# as3320-BandPass.net
KiCad netlist of a schematic drawn in EAGLE
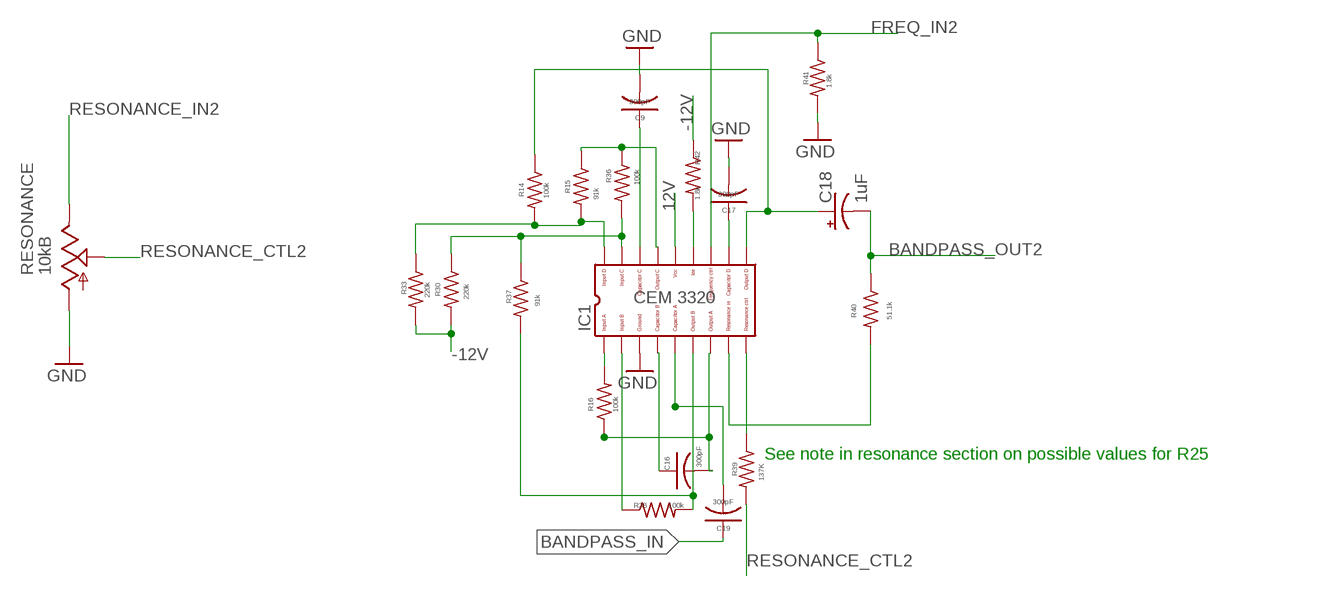
[diagram p0: schematic, sheet 1]
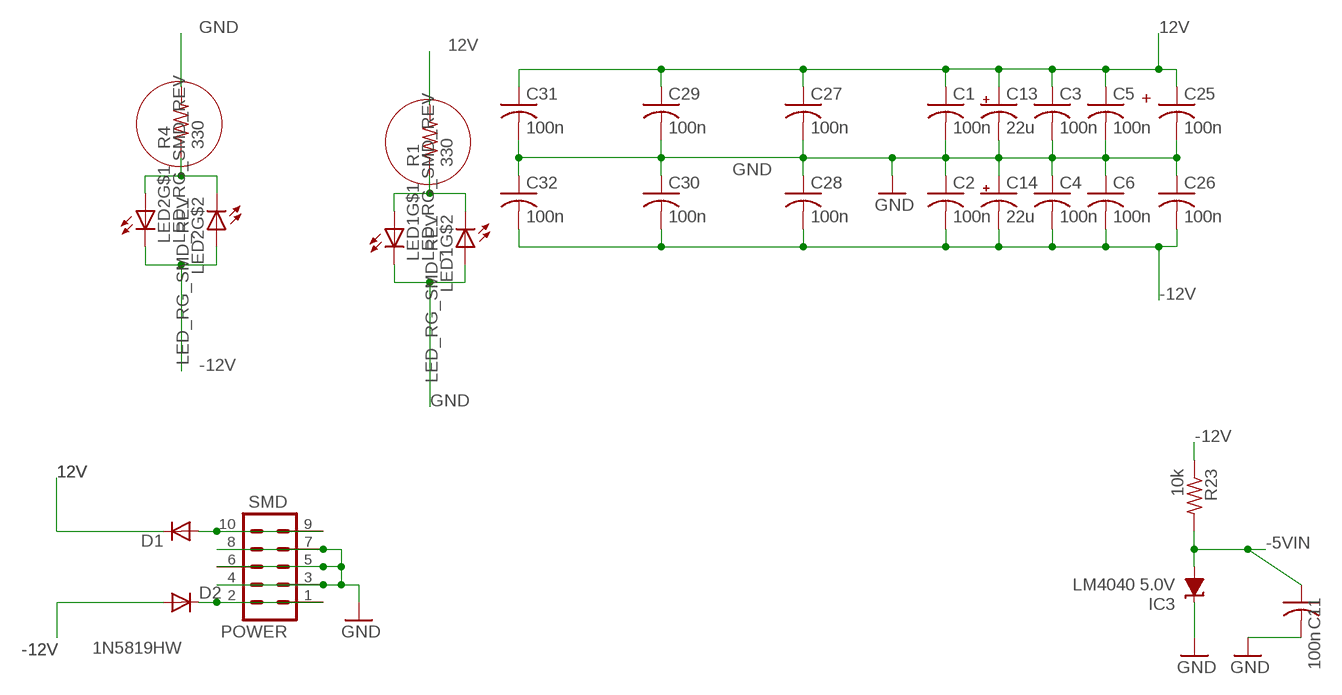
[diagram p1: schematic, sheet 2]
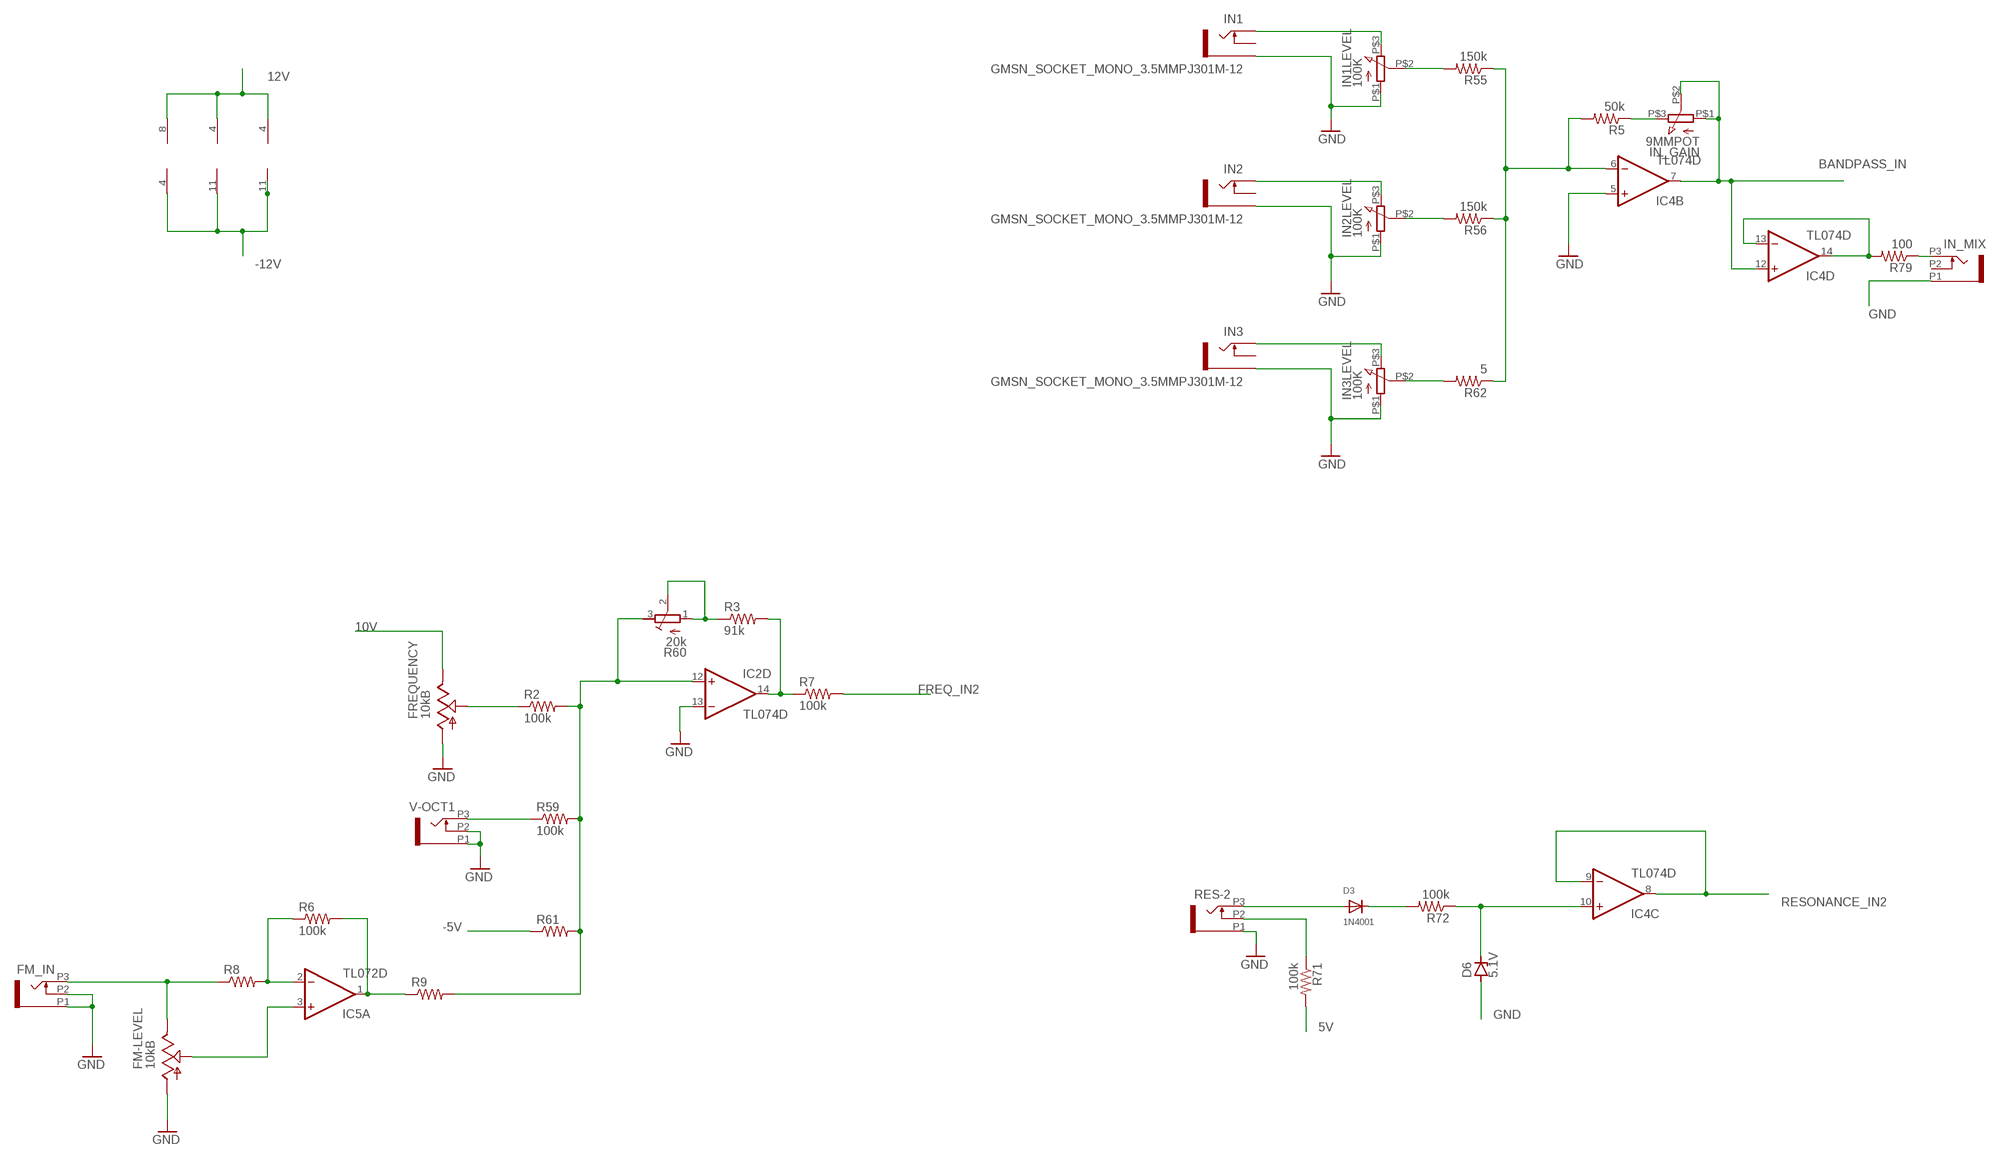
[diagram p2: schematic, sheet 3]
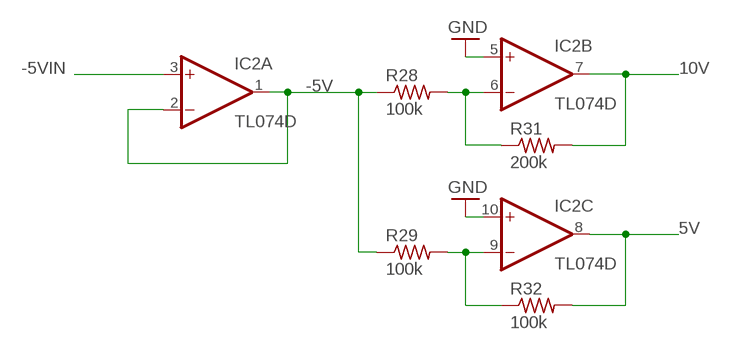
[diagram p3: schematic, sheet 4]
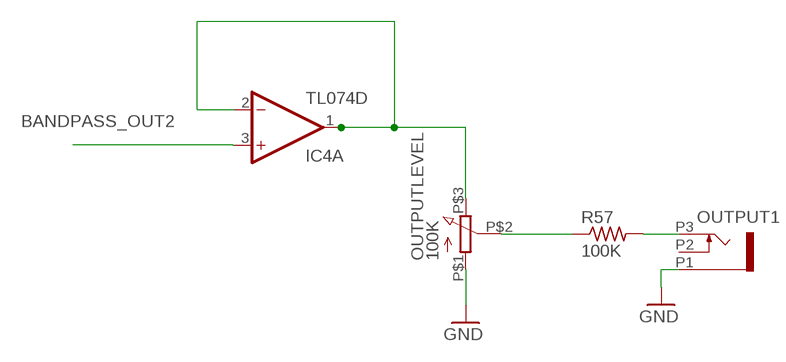
[diagram p4: schematic, sheet 5]

(export (version "E")
  (design (tool "Eeschema 10.0.6"))
  (components
    (comp (ref "C1")
      (value "100n")
      (footprint "eagle-import:C0805K")
      (libsource (lib "eagle-import") (part "C-USC0805K"))
    )
    (comp (ref "C2")
      (value "100n")
      (footprint "eagle-import:C0805K")
      (libsource (lib "eagle-import") (part "C-USC0805K"))
    )
    (comp (ref "C3")
      (value "100n")
      (footprint "eagle-import:C0805K")
      (libsource (lib "eagle-import") (part "C-USC0805K"))
    )
    (comp (ref "C4")
      (value "100n")
      (footprint "eagle-import:C0805K")
      (libsource (lib "eagle-import") (part "C-USC0805K"))
    )
    (comp (ref "C5")
      (value "100n")
      (footprint "eagle-import:C0805K")
      (libsource (lib "eagle-import") (part "C-USC0805K"))
    )
    (comp (ref "C6")
      (value "100n")
      (footprint "eagle-import:C0805K")
      (libsource (lib "eagle-import") (part "C-USC0805K"))
    )
    (comp (ref "C11")
      (value "100n")
      (footprint "eagle-import:GMSN_C0805K")
      (libsource (lib "eagle-import") (part "GMSN_C-USC0805K"))
    )
    (comp (ref "C13")
      (value "22u")
      (footprint "eagle-import:PANASONIC_B")
      (libsource (lib "eagle-import") (part "CPOL-USB"))
    )
    (comp (ref "C14")
      (value "22u")
      (footprint "eagle-import:PANASONIC_B")
      (libsource (lib "eagle-import") (part "CPOL-USB"))
    )
    (comp (ref "C25")
      (value "100n")
      (footprint "eagle-import:C0805K")
      (libsource (lib "eagle-import") (part "C-USC0805K"))
    )
    (comp (ref "C26")
      (value "100n")
      (footprint "eagle-import:C0805K")
      (libsource (lib "eagle-import") (part "C-USC0805K"))
    )
    (comp (ref "C27")
      (value "100n")
      (footprint "eagle-import:C0805K")
      (libsource (lib "eagle-import") (part "C-USC0805K"))
    )
    (comp (ref "C28")
      (value "100n")
      (footprint "eagle-import:C0805K")
      (libsource (lib "eagle-import") (part "C-USC0805K"))
    )
    (comp (ref "C29")
      (value "100n")
      (footprint "eagle-import:C0805K")
      (libsource (lib "eagle-import") (part "C-USC0805K"))
    )
    (comp (ref "C30")
      (value "100n")
      (footprint "eagle-import:C0805K")
      (libsource (lib "eagle-import") (part "C-USC0805K"))
    )
    (comp (ref "C31")
      (value "100n")
      (footprint "eagle-import:C0805K")
      (libsource (lib "eagle-import") (part "C-USC0805K"))
    )
    (comp (ref "C32")
      (value "100n")
      (footprint "eagle-import:C0805K")
      (libsource (lib "eagle-import") (part "C-USC0805K"))
    )
    (comp (ref "D1")
      (value "1N5819HW")
      (footprint "eagle-import:SOD123")
      (libsource (lib "eagle-import") (part "DIODE-SOD123"))
    )
    (comp (ref "D2")
      (value "1N5819HW")
      (footprint "eagle-import:SOD123")
      (libsource (lib "eagle-import") (part "DIODE-SOD123"))
    )
    (comp (ref "IC3")
      (value "LM4040 5.0V")
      (footprint "eagle-import:DBZ_R-PDSO-G3")
      (libsource (lib "eagle-import") (part "LM4041DBZC12"))
    )
    (comp (ref "LED1")
      (value "LED_RG_SMD_REV")
      (footprint "eagle-import:LSG_T77K")
      (fields (field (name "RS-PART") "915-4828"))
      (libsource (lib "eagle-import") (part "LED_RG_SMD_REV"))
    )
    (comp (ref "LED2")
      (value "LED_RG_SMD_REV")
      (footprint "eagle-import:LSG_T77K")
      (libsource (lib "eagle-import") (part "LED_RG_SMD_REV"))
    )
    (comp (ref "POWER")
      (value "SMD")
      (footprint "eagle-import:2X5-SHROUDED_SMD")
      (fields (field (name "RS-PART") "828-1783"))
      (libsource (lib "eagle-import") (part "CONN_05X2SHD_SMD"))
    )
    (comp (ref "R1")
      (value "330")
      (footprint "eagle-import:GMSN_M0805")
      (libsource (lib "eagle-import") (part "GMSN_R-US_M0805"))
    )
    (comp (ref "R4")
      (value "330")
      (footprint "eagle-import:GMSN_M0805")
      (fields (field (name "RS-PART") "915-4828"))
      (libsource (lib "eagle-import") (part "GMSN_R-US_M0805"))
    )
    (comp (ref "R23")
      (value "10k")
      (footprint "eagle-import:GMSN_M0805")
      (libsource (lib "eagle-import") (part "GMSN_R-US_M0805"))
    )
    (comp (ref "IC4")
      (value "TL074D")
      (footprint "eagle-import:SO14")
      (libsource (lib "eagle-import") (part "TL074D"))
    )
    (comp (ref "OUTPUT1")
      (value "PJ301_THONKICONN6")
      (footprint "eagle-import:WQP_PJ_301M6")
      (libsource (lib "eagle-import") (part "PJ301_THONKICONN6"))
    )
    (comp (ref "OUTPUTLEVEL")
      (value "100K")
      (footprint "eagle-import:POT")
      (libsource (lib "eagle-import") (part "9MMPOT"))
    )
    (comp (ref "R57")
      (value "100K")
      (footprint "eagle-import:GMSN_M0805")
      (libsource (lib "eagle-import") (part "GMSN_R-US_M0805"))
    )
    (comp (ref "D3")
      (value "1N4001")
      (footprint "eagle-import:SMADIODE")
      (libsource (lib "eagle-import") (part "DIODESMA"))
    )
    (comp (ref "D6")
      (value "5.1V")
      (footprint "eagle-import:SOT23")
      (fields (field (name "RS-PART") "816-7962"))
      (libsource (lib "eagle-import") (part "ZENER-DIODESOT23"))
    )
    (comp (ref "FM-LEVEL")
      (value "10kB")
      (footprint "eagle-import:ALPS_POT_VERTICAL")
      (libsource (lib "eagle-import") (part "POT_USVERTICAL"))
    )
    (comp (ref "FM_IN")
      (value "PJ301_THONKICONN6")
      (footprint "eagle-import:WQP_PJ_301M6")
      (libsource (lib "eagle-import") (part "PJ301_THONKICONN6"))
    )
    (comp (ref "FREQUENCY")
      (value "10kB")
      (footprint "eagle-import:ALPS_POT_VERTICAL")
      (libsource (lib "eagle-import") (part "POT_USVERTICAL"))
    )
    (comp (ref "IC2")
      (value "TL074D")
      (footprint "eagle-import:SO14")
      (libsource (lib "eagle-import") (part "linear_262_TL074D"))
    )
    (comp (ref "IC5")
      (value "TL072D")
      (footprint "eagle-import:SO08")
      (libsource (lib "eagle-import") (part "TL072D"))
    )
    (comp (ref "IN1")
      (value "GMSN_SOCKET_MONO_3.5MMPJ301M-12")
      (footprint "eagle-import:GMSN_PJ301M-12")
      (libsource (lib "eagle-import") (part "GMSN_SOCKET_MONO_3.5MMPJ301M-12"))
    )
    (comp (ref "IN1LEVEL")
      (value "100K")
      (footprint "eagle-import:POT")
      (libsource (lib "eagle-import") (part "9MMPOT"))
    )
    (comp (ref "IN2")
      (value "GMSN_SOCKET_MONO_3.5MMPJ301M-12")
      (footprint "eagle-import:GMSN_PJ301M-12")
      (libsource (lib "eagle-import") (part "GMSN_SOCKET_MONO_3.5MMPJ301M-12"))
    )
    (comp (ref "IN2LEVEL")
      (value "100K")
      (footprint "eagle-import:POT")
      (libsource (lib "eagle-import") (part "9MMPOT"))
    )
    (comp (ref "IN3")
      (value "GMSN_SOCKET_MONO_3.5MMPJ301M-12")
      (footprint "eagle-import:GMSN_PJ301M-12")
      (libsource (lib "eagle-import") (part "GMSN_SOCKET_MONO_3.5MMPJ301M-12"))
    )
    (comp (ref "IN3LEVEL")
      (value "100K")
      (footprint "eagle-import:POT")
      (libsource (lib "eagle-import") (part "9MMPOT"))
    )
    (comp (ref "IN_GAIN")
      (value "9MMPOT")
      (footprint "eagle-import:POT")
      (libsource (lib "eagle-import") (part "9MMPOT"))
    )
    (comp (ref "IN_MIX")
      (value "PJ301_THONKICONN6")
      (footprint "eagle-import:WQP_PJ_301M6")
      (libsource (lib "eagle-import") (part "PJ301_THONKICONN6"))
    )
    (comp (ref "R2")
      (value "100k")
      (footprint "eagle-import:GMSN_M0805")
      (libsource (lib "eagle-import") (part "GMSN_R-US_M0805"))
    )
    (comp (ref "R3")
      (value "91k")
      (footprint "eagle-import:GMSN_M0805")
      (libsource (lib "eagle-import") (part "GMSN_R-US_M0805"))
    )
    (comp (ref "R5")
      (value "50k")
      (footprint "eagle-import:GMSN_M0805")
      (libsource (lib "eagle-import") (part "GMSN_R-US_M0805"))
    )
    (comp (ref "R6")
      (value "100k")
      (footprint "eagle-import:GMSN_M0805")
      (libsource (lib "eagle-import") (part "GMSN_R-US_M0805"))
    )
    (comp (ref "R7")
      (value "100k")
      (footprint "eagle-import:GMSN_M0805")
      (libsource (lib "eagle-import") (part "GMSN_R-US_M0805"))
    )
    (comp (ref "R8")
      (value "62k")
      (footprint "eagle-import:GMSN_M0805")
      (libsource (lib "eagle-import") (part "GMSN_R-US_M0805"))
    )
    (comp (ref "R9")
      (value "62k")
      (footprint "eagle-import:GMSN_M0805")
      (libsource (lib "eagle-import") (part "GMSN_R-US_M0805"))
    )
    (comp (ref "R55")
      (value "150k")
      (footprint "eagle-import:R0805")
      (libsource (lib "eagle-import") (part "GMSN_R-US_R0805"))
    )
    (comp (ref "R56")
      (value "150k")
      (footprint "eagle-import:R0805")
      (libsource (lib "eagle-import") (part "GMSN_R-US_R0805"))
    )
    (comp (ref "R59")
      (value "100k")
      (footprint "eagle-import:GMSN_M0805")
      (libsource (lib "eagle-import") (part "GMSN_R-US_M0805"))
    )
    (comp (ref "R60")
      (value "20k")
      (footprint "eagle-import:RTRIM3296X")
      (libsource (lib "eagle-import") (part "R-TRIMM3296X"))
    )
    (comp (ref "R61")
      (value "62k")
      (footprint "eagle-import:GMSN_M0805")
      (libsource (lib "eagle-import") (part "GMSN_R-US_M0805"))
    )
    (comp (ref "R62")
      (value "5")
      (footprint "eagle-import:R0805")
      (libsource (lib "eagle-import") (part "GMSN_R-US_R0805"))
    )
    (comp (ref "R71")
      (value "100k")
      (footprint "eagle-import:R0805")
      (libsource (lib "eagle-import") (part "GMSN_R-US_R0805"))
    )
    (comp (ref "R72")
      (value "100k")
      (footprint "eagle-import:GMSN_M0805")
      (libsource (lib "eagle-import") (part "GMSN_R-US_M0805"))
    )
    (comp (ref "R79")
      (value "100")
      (footprint "eagle-import:GMSN_M0805")
      (libsource (lib "eagle-import") (part "GMSN_R-US_M0805"))
    )
    (comp (ref "RES-2")
      (value "PJ301_THONKICONN6")
      (footprint "eagle-import:WQP_PJ_301M6")
      (libsource (lib "eagle-import") (part "PJ301_THONKICONN6"))
    )
    (comp (ref "V-OCT1")
      (value "PJ301_THONKICONN6")
      (footprint "eagle-import:WQP_PJ_301M6")
      (libsource (lib "eagle-import") (part "PJ301_THONKICONN6"))
    )
    (comp (ref "C9")
      (value "300pF")
      (footprint "eagle-import:C0805K")
      (libsource (lib "eagle-import") (part "C-USC0805K"))
    )
    (comp (ref "C16")
      (value "300pF")
      (footprint "eagle-import:C0805K")
      (libsource (lib "eagle-import") (part "C-USC0805K"))
    )
    (comp (ref "C17")
      (value "300pF")
      (footprint "eagle-import:C0805K")
      (libsource (lib "eagle-import") (part "C-USC0805K"))
    )
    (comp (ref "C18")
      (value "1uF")
      (footprint "eagle-import:PANASONIC_B")
      (libsource (lib "eagle-import") (part "rcl_334_CPOL-USB"))
    )
    (comp (ref "C19")
      (value "300pF")
      (footprint "eagle-import:C0805K")
      (libsource (lib "eagle-import") (part "C-USC0805K"))
    )
    (comp (ref "IC1")
      (value "CEM3320")
      (footprint "eagle-import:DIL18")
      (libsource (lib "eagle-import") (part "CEM3320"))
    )
    (comp (ref "R14")
      (value "100k")
      (footprint "eagle-import:GMSN_M0805")
      (libsource (lib "eagle-import") (part "GMSN_R-US_M0805"))
    )
    (comp (ref "R15")
      (value "91k")
      (footprint "eagle-import:GMSN_M0805")
      (libsource (lib "eagle-import") (part "GMSN_R-US_M0805"))
    )
    (comp (ref "R16")
      (value "100k")
      (footprint "eagle-import:GMSN_M0805")
      (libsource (lib "eagle-import") (part "GMSN_R-US_M0805"))
    )
    (comp (ref "R30")
      (value "220k")
      (footprint "eagle-import:GMSN_M0805")
      (libsource (lib "eagle-import") (part "GMSN_R-US_M0805"))
    )
    (comp (ref "R33")
      (value "220k")
      (footprint "eagle-import:GMSN_M0805")
      (libsource (lib "eagle-import") (part "GMSN_R-US_M0805"))
    )
    (comp (ref "R36")
      (value "100k")
      (footprint "eagle-import:GMSN_M0805")
      (libsource (lib "eagle-import") (part "GMSN_R-US_M0805"))
    )
    (comp (ref "R37")
      (value "91k")
      (footprint "eagle-import:GMSN_M0805")
      (libsource (lib "eagle-import") (part "GMSN_R-US_M0805"))
    )
    (comp (ref "R38")
      (value "100k")
      (footprint "eagle-import:GMSN_M0805")
      (libsource (lib "eagle-import") (part "GMSN_R-US_M0805"))
    )
    (comp (ref "R39")
      (value "137K")
      (footprint "eagle-import:GMSN_M0805")
      (libsource (lib "eagle-import") (part "GMSN_R-US_M0805"))
    )
    (comp (ref "R40")
      (value "51.1k")
      (footprint "eagle-import:GMSN_M0805")
      (libsource (lib "eagle-import") (part "GMSN_R-US_M0805"))
    )
    (comp (ref "R41")
      (value "1.8k")
      (footprint "eagle-import:GMSN_M0805")
      (libsource (lib "eagle-import") (part "GMSN_R-US_M0805"))
    )
    (comp (ref "R42")
      (value "1.8k")
      (footprint "eagle-import:GMSN_M0805")
      (libsource (lib "eagle-import") (part "GMSN_R-US_M0805"))
    )
    (comp (ref "RESONANCE")
      (value "10kB")
      (footprint "eagle-import:ALPS_POT_VERTICAL")
      (libsource (lib "eagle-import") (part "POT_USVERTICAL"))
    )
    (comp (ref "R28")
      (value "100k")
      (footprint "eagle-import:GMSN_M0805")
      (libsource (lib "eagle-import") (part "GMSN_R-US_M0805"))
    )
    (comp (ref "R29")
      (value "100k")
      (footprint "eagle-import:GMSN_M0805")
      (libsource (lib "eagle-import") (part "GMSN_R-US_M0805"))
    )
    (comp (ref "R31")
      (value "200k")
      (footprint "eagle-import:GMSN_M0805")
      (libsource (lib "eagle-import") (part "GMSN_R-US_M0805"))
    )
    (comp (ref "R32")
      (value "100k")
      (footprint "eagle-import:GMSN_M0805")
      (libsource (lib "eagle-import") (part "GMSN_R-US_M0805"))
    )
  )
  (nets
    (net (code "1") (name "-5V") (class "Default")
      (node (ref "IC2") (pin "1") (pinfunction "OUT_1") (pintype "output"))
      (node (ref "IC2") (pin "2") (pinfunction "-IN_2") (pintype "input"))
      (node (ref "R28") (pin "1") (pinfunction "1_1") (pintype "passive"))
      (node (ref "R29") (pin "1") (pinfunction "1_1") (pintype "passive"))
      (node (ref "R61") (pin "1") (pinfunction "1_1") (pintype "passive"))
    )
    (net (code "2") (name "-5VIN") (class "Default")
      (node (ref "C11") (pin "1") (pinfunction "1_1") (pintype "passive"))
      (node (ref "IC2") (pin "3") (pinfunction "+IN_3") (pintype "input"))
      (node (ref "IC3") (pin "2") (pinfunction "A_2") (pintype "passive"))
      (node (ref "R23") (pin "2") (pinfunction "2_2") (pintype "passive"))
    )
    (net (code "3") (name "-12V") (class "Default")
      (node (ref "C14") (pin "-") (pinfunction "-_-") (pintype "passive"))
      (node (ref "C2") (pin "2") (pinfunction "2_2") (pintype "passive"))
      (node (ref "C26") (pin "2") (pinfunction "2_2") (pintype "passive"))
      (node (ref "C28") (pin "2") (pinfunction "2_2") (pintype "passive"))
      (node (ref "C30") (pin "2") (pinfunction "2_2") (pintype "passive"))
      (node (ref "C32") (pin "2") (pinfunction "2_2") (pintype "passive"))
      (node (ref "C4") (pin "2") (pinfunction "2_2") (pintype "passive"))
      (node (ref "C6") (pin "2") (pinfunction "2_2") (pintype "passive"))
      (node (ref "D2") (pin "A") (pinfunction "A_A") (pintype "passive"))
      (node (ref "IC2") (pin "11") (pinfunction "V-_11") (pintype "power_in"))
      (node (ref "IC4") (pin "11") (pinfunction "V-_11") (pintype "power_in"))
      (node (ref "IC5") (pin "4") (pinfunction "V-_4") (pintype "power_in"))
      (node (ref "LED2") (pin "1") (pinfunction "C_1") (pintype "passive"))
      (node (ref "LED2") (pin "4") (pinfunction "A_4") (pintype "passive"))
      (node (ref "R23") (pin "1") (pinfunction "1_1") (pintype "passive"))
      (node (ref "R30") (pin "2") (pinfunction "2_2") (pintype "passive"))
      (node (ref "R33") (pin "2") (pinfunction "2_2") (pintype "passive"))
      (node (ref "R42") (pin "1") (pinfunction "1_1") (pintype "passive"))
    )
    (net (code "4") (name "5V") (class "Default")
      (node (ref "IC2") (pin "8") (pinfunction "OUT_8") (pintype "output"))
      (node (ref "R32") (pin "2") (pinfunction "2_2") (pintype "passive"))
      (node (ref "R71") (pin "2") (pinfunction "2_2") (pintype "passive"))
    )
    (net (code "5") (name "10V") (class "Default")
      (node (ref "FREQUENCY") (pin "P$1") (pinfunction "E_P$1") (pintype "passive"))
      (node (ref "IC2") (pin "7") (pinfunction "OUT_7") (pintype "output"))
      (node (ref "R31") (pin "2") (pinfunction "2_2") (pintype "passive"))
    )
    (net (code "6") (name "12V") (class "Default")
      (node (ref "C1") (pin "1") (pinfunction "1_1") (pintype "passive"))
      (node (ref "C13") (pin "+") (pinfunction "+_+") (pintype "passive"))
      (node (ref "C25") (pin "1") (pinfunction "1_1") (pintype "passive"))
      (node (ref "C27") (pin "1") (pinfunction "1_1") (pintype "passive"))
      (node (ref "C29") (pin "1") (pinfunction "1_1") (pintype "passive"))
      (node (ref "C3") (pin "1") (pinfunction "1_1") (pintype "passive"))
      (node (ref "C31") (pin "1") (pinfunction "1_1") (pintype "passive"))
      (node (ref "C5") (pin "1") (pinfunction "1_1") (pintype "passive"))
      (node (ref "D1") (pin "C") (pinfunction "C_C") (pintype "passive"))
      (node (ref "IC1") (pin "14") (pinfunction "14_14") (pintype "power_in"))
      (node (ref "IC2") (pin "4") (pinfunction "V+_4") (pintype "power_in"))
      (node (ref "IC4") (pin "4") (pinfunction "V+_4") (pintype "power_in"))
      (node (ref "IC5") (pin "8") (pinfunction "V+_8") (pintype "power_in"))
      (node (ref "R1") (pin "2") (pinfunction "2_2") (pintype "passive"))
    )
    (net (code "7") (name "BANDPASS_IN") (class "Default")
      (node (ref "C19") (pin "1") (pinfunction "1_1") (pintype "passive"))
      (node (ref "IC4") (pin "12") (pinfunction "+IN_12") (pintype "input"))
      (node (ref "IC4") (pin "7") (pinfunction "OUT_7") (pintype "output"))
      (node (ref "IN_GAIN") (pin "P$1") (pinfunction "1_P$1") (pintype "passive"))
      (node (ref "IN_GAIN") (pin "P$2") (pinfunction "2_P$2") (pintype "passive"))
    )
    (net (code "8") (name "BANDPASS_OUT2") (class "Default")
      (node (ref "C18") (pin "-") (pinfunction "-_-") (pintype "passive"))
      (node (ref "IC4") (pin "3") (pinfunction "+IN_3") (pintype "input"))
      (node (ref "R40") (pin "1") (pinfunction "1_1") (pintype "passive"))
    )
    (net (code "9") (name "FREQ_IN2") (class "Default")
      (node (ref "IC1") (pin "12") (pinfunction "12_12") (pintype "bidirectional"))
      (node (ref "R41") (pin "1") (pinfunction "1_1") (pintype "passive"))
      (node (ref "R7") (pin "2") (pinfunction "2_2") (pintype "passive"))
    )
    (net (code "10") (name "GND") (class "Default")
      (node (ref "C1") (pin "2") (pinfunction "2_2") (pintype "passive"))
      (node (ref "C11") (pin "2") (pinfunction "2_2") (pintype "passive"))
      (node (ref "C13") (pin "-") (pinfunction "-_-") (pintype "passive"))
      (node (ref "C14") (pin "+") (pinfunction "+_+") (pintype "passive"))
      (node (ref "C17") (pin "2") (pinfunction "2_2") (pintype "passive"))
      (node (ref "C2") (pin "1") (pinfunction "1_1") (pintype "passive"))
      (node (ref "C25") (pin "2") (pinfunction "2_2") (pintype "passive"))
      (node (ref "C26") (pin "1") (pinfunction "1_1") (pintype "passive"))
      (node (ref "C27") (pin "2") (pinfunction "2_2") (pintype "passive"))
      (node (ref "C28") (pin "1") (pinfunction "1_1") (pintype "passive"))
      (node (ref "C29") (pin "2") (pinfunction "2_2") (pintype "passive"))
      (node (ref "C3") (pin "2") (pinfunction "2_2") (pintype "passive"))
      (node (ref "C30") (pin "1") (pinfunction "1_1") (pintype "passive"))
      (node (ref "C31") (pin "2") (pinfunction "2_2") (pintype "passive"))
      (node (ref "C32") (pin "1") (pinfunction "1_1") (pintype "passive"))
      (node (ref "C4") (pin "1") (pinfunction "1_1") (pintype "passive"))
      (node (ref "C5") (pin "2") (pinfunction "2_2") (pintype "passive"))
      (node (ref "C6") (pin "1") (pinfunction "1_1") (pintype "passive"))
      (node (ref "C9") (pin "2") (pinfunction "2_2") (pintype "passive"))
      (node (ref "D6") (pin "1") (pinfunction "A_1") (pintype "passive"))
      (node (ref "FM-LEVEL") (pin "P$3") (pinfunction "A_P$3") (pintype "passive"))
      (node (ref "FM_IN") (pin "P1") (pinfunction "1_P1") (pintype "passive"))
      (node (ref "FM_IN") (pin "P2") (pinfunction "2_P2") (pintype "passive"))
      (node (ref "FREQUENCY") (pin "P$3") (pinfunction "A_P$3") (pintype "passive"))
      (node (ref "IC1") (pin "3") (pinfunction "3_3") (pintype "power_in"))
      (node (ref "IC2") (pin "10") (pinfunction "+IN_10") (pintype "input"))
      (node (ref "IC2") (pin "13") (pinfunction "-IN_13") (pintype "input"))
      (node (ref "IC2") (pin "5") (pinfunction "+IN_5") (pintype "input"))
      (node (ref "IC3") (pin "1") (pinfunction "C_1") (pintype "passive"))
      (node (ref "IC4") (pin "5") (pinfunction "+IN_5") (pintype "input"))
      (node (ref "IN1") (pin "GND") (pinfunction "SLEEVE_GND") (pintype "passive"))
      (node (ref "IN1LEVEL") (pin "P$1") (pinfunction "1_P$1") (pintype "passive"))
      (node (ref "IN2") (pin "GND") (pinfunction "SLEEVE_GND") (pintype "passive"))
      (node (ref "IN2LEVEL") (pin "P$1") (pinfunction "1_P$1") (pintype "passive"))
      (node (ref "IN3") (pin "GND") (pinfunction "SLEEVE_GND") (pintype "passive"))
      (node (ref "IN3LEVEL") (pin "P$1") (pinfunction "1_P$1") (pintype "passive"))
      (node (ref "IN_MIX") (pin "P1") (pinfunction "1_P1") (pintype "passive"))
      (node (ref "LED1") (pin "1") (pinfunction "C_1") (pintype "passive"))
      (node (ref "LED1") (pin "4") (pinfunction "A_4") (pintype "passive"))
      (node (ref "OUTPUT1") (pin "P1") (pinfunction "1_P1") (pintype "passive"))
      (node (ref "OUTPUTLEVEL") (pin "P$1") (pinfunction "1_P$1") (pintype "passive"))
      (node (ref "POWER") (pin "3") (pinfunction "3_3") (pintype "passive"))
      (node (ref "POWER") (pin "4") (pinfunction "4_4") (pintype "passive"))
      (node (ref "POWER") (pin "5") (pinfunction "5_5") (pintype "passive"))
      (node (ref "POWER") (pin "6") (pinfunction "6_6") (pintype "passive"))
      (node (ref "POWER") (pin "7") (pinfunction "7_7") (pintype "passive"))
      (node (ref "POWER") (pin "8") (pinfunction "8_8") (pintype "passive"))
      (node (ref "R4") (pin "2") (pinfunction "2_2") (pintype "passive"))
      (node (ref "R41") (pin "2") (pinfunction "2_2") (pintype "passive"))
      (node (ref "RES-2") (pin "P1") (pinfunction "1_P1") (pintype "passive"))
      (node (ref "RESONANCE") (pin "P$3") (pinfunction "A_P$3") (pintype "passive"))
      (node (ref "V-OCT1") (pin "P1") (pinfunction "1_P1") (pintype "passive"))
      (node (ref "V-OCT1") (pin "P2") (pinfunction "2_P2") (pintype "passive"))
    )
    (net (code "11") (name "Net-(C9-Pad1)") (class "Default")
      (node (ref "C9") (pin "1") (pinfunction "1_1") (pintype "passive"))
      (node (ref "IC1") (pin "16") (pinfunction "16_16") (pintype "bidirectional"))
    )
    (net (code "12") (name "Net-(C16-Pad1)") (class "Default")
      (node (ref "C16") (pin "1") (pinfunction "1_1") (pintype "passive"))
      (node (ref "IC1") (pin "4") (pinfunction "4_4") (pintype "bidirectional"))
    )
    (net (code "13") (name "Net-(C16-Pad2)") (class "Default")
      (node (ref "C16") (pin "2") (pinfunction "2_2") (pintype "passive"))
      (node (ref "IC1") (pin "7") (pinfunction "7_7") (pintype "output"))
      (node (ref "R16") (pin "1") (pinfunction "1_1") (pintype "passive"))
    )
    (net (code "14") (name "Net-(C17-Pad1)") (class "Default")
      (node (ref "C17") (pin "1") (pinfunction "1_1") (pintype "passive"))
      (node (ref "IC1") (pin "11") (pinfunction "11_11") (pintype "output"))
    )
    (net (code "15") (name "Net-(C18-Pad+)") (class "Default")
      (node (ref "C18") (pin "+") (pinfunction "+_+") (pintype "passive"))
      (node (ref "IC1") (pin "10") (pinfunction "10_10") (pintype "output"))
      (node (ref "R14") (pin "1") (pinfunction "1_1") (pintype "passive"))
    )
    (net (code "16") (name "Net-(C19-Pad2)") (class "Default")
      (node (ref "C19") (pin "2") (pinfunction "2_2") (pintype "passive"))
      (node (ref "IC1") (pin "5") (pinfunction "5_5") (pintype "bidirectional"))
    )
    (net (code "17") (name "Net-(D1-PadA)") (class "Default")
      (node (ref "D1") (pin "A") (pinfunction "A_A") (pintype "passive"))
      (node (ref "POWER") (pin "10") (pinfunction "10_10") (pintype "passive"))
      (node (ref "POWER") (pin "9") (pinfunction "9_9") (pintype "passive"))
    )
    (net (code "18") (name "Net-(D2-PadC)") (class "Default")
      (node (ref "D2") (pin "C") (pinfunction "C_C") (pintype "passive"))
      (node (ref "POWER") (pin "1") (pinfunction "1_1") (pintype "passive"))
      (node (ref "POWER") (pin "2") (pinfunction "2_2") (pintype "passive"))
    )
    (net (code "19") (name "Net-(D3-PadC)") (class "Default")
      (node (ref "D3") (pin "C") (pinfunction "C_C") (pintype "passive"))
      (node (ref "R72") (pin "2") (pinfunction "2_2") (pintype "passive"))
    )
    (net (code "20") (name "Net-(D6-C)") (class "Default")
      (node (ref "D6") (pin "3") (pinfunction "C_3") (pintype "passive"))
      (node (ref "IC4") (pin "10") (pinfunction "+IN_10") (pintype "input"))
      (node (ref "R72") (pin "1") (pinfunction "1_1") (pintype "passive"))
    )
    (net (code "21") (name "Net-(FM-LEVEL-E)") (class "Default")
      (node (ref "FM-LEVEL") (pin "P$1") (pinfunction "E_P$1") (pintype "passive"))
      (node (ref "FM_IN") (pin "P3") (pinfunction "3_P3") (pintype "passive"))
      (node (ref "R8") (pin "1") (pinfunction "1_1") (pintype "passive"))
    )
    (net (code "22") (name "Net-(FM-LEVEL-S)") (class "Default")
      (node (ref "FM-LEVEL") (pin "P$2") (pinfunction "S_P$2") (pintype "passive"))
      (node (ref "IC5") (pin "3") (pinfunction "+IN_3") (pintype "input"))
    )
    (net (code "23") (name "Net-(FREQUENCY-S)") (class "Default")
      (node (ref "FREQUENCY") (pin "P$2") (pinfunction "S_P$2") (pintype "passive"))
      (node (ref "R2") (pin "1") (pinfunction "1_1") (pintype "passive"))
    )
    (net (code "24") (name "Net-(IC1-Pad1)") (class "Default")
      (node (ref "IC1") (pin "1") (pinfunction "1_1") (pintype "input"))
      (node (ref "R16") (pin "2") (pinfunction "2_2") (pintype "passive"))
    )
    (net (code "25") (name "Net-(IC1-Pad2)") (class "Default")
      (node (ref "IC1") (pin "2") (pinfunction "2_2") (pintype "input"))
      (node (ref "R38") (pin "1") (pinfunction "1_1") (pintype "passive"))
    )
    (net (code "26") (name "Net-(IC1-Pad6)") (class "Default")
      (node (ref "IC1") (pin "6") (pinfunction "6_6") (pintype "output"))
      (node (ref "R37") (pin "2") (pinfunction "2_2") (pintype "passive"))
      (node (ref "R38") (pin "2") (pinfunction "2_2") (pintype "passive"))
    )
    (net (code "27") (name "Net-(IC1-Pad8)") (class "Default")
      (node (ref "IC1") (pin "8") (pinfunction "8_8") (pintype "input"))
      (node (ref "R40") (pin "2") (pinfunction "2_2") (pintype "passive"))
    )
    (net (code "28") (name "Net-(IC1-Pad9)") (class "Default")
      (node (ref "IC1") (pin "9") (pinfunction "9_9") (pintype "input"))
      (node (ref "R39") (pin "1") (pinfunction "1_1") (pintype "passive"))
    )
    (net (code "29") (name "Net-(IC1-Pad13)") (class "Default")
      (node (ref "IC1") (pin "13") (pinfunction "13_13") (pintype "power_in"))
      (node (ref "R42") (pin "2") (pinfunction "2_2") (pintype "passive"))
    )
    (net (code "30") (name "Net-(IC1-Pad15)") (class "Default")
      (node (ref "IC1") (pin "15") (pinfunction "15_15") (pintype "output"))
      (node (ref "R15") (pin "1") (pinfunction "1_1") (pintype "passive"))
      (node (ref "R36") (pin "1") (pinfunction "1_1") (pintype "passive"))
    )
    (net (code "31") (name "Net-(IC1-Pad17)") (class "Default")
      (node (ref "IC1") (pin "17") (pinfunction "17_17") (pintype "input"))
      (node (ref "R30") (pin "1") (pinfunction "1_1") (pintype "passive"))
      (node (ref "R36") (pin "2") (pinfunction "2_2") (pintype "passive"))
      (node (ref "R37") (pin "1") (pinfunction "1_1") (pintype "passive"))
    )
    (net (code "32") (name "Net-(IC1-Pad18)") (class "Default")
      (node (ref "IC1") (pin "18") (pinfunction "18_18") (pintype "input"))
      (node (ref "R14") (pin "2") (pinfunction "2_2") (pintype "passive"))
      (node (ref "R15") (pin "2") (pinfunction "2_2") (pintype "passive"))
      (node (ref "R33") (pin "1") (pinfunction "1_1") (pintype "passive"))
    )
    (net (code "33") (name "Net-(IC2B--IN)") (class "Default")
      (node (ref "IC2") (pin "6") (pinfunction "-IN_6") (pintype "input"))
      (node (ref "R28") (pin "2") (pinfunction "2_2") (pintype "passive"))
      (node (ref "R31") (pin "1") (pinfunction "1_1") (pintype "passive"))
    )
    (net (code "34") (name "Net-(IC2C--IN)") (class "Default")
      (node (ref "IC2") (pin "9") (pinfunction "-IN_9") (pintype "input"))
      (node (ref "R29") (pin "2") (pinfunction "2_2") (pintype "passive"))
      (node (ref "R32") (pin "1") (pinfunction "1_1") (pintype "passive"))
    )
    (net (code "35") (name "Net-(IC2D-+IN)") (class "Default")
      (node (ref "IC2") (pin "12") (pinfunction "+IN_12") (pintype "input"))
      (node (ref "R2") (pin "2") (pinfunction "2_2") (pintype "passive"))
      (node (ref "R59") (pin "2") (pinfunction "2_2") (pintype "passive"))
      (node (ref "R60") (pin "3") (pinfunction "A_3") (pintype "passive"))
      (node (ref "R61") (pin "2") (pinfunction "2_2") (pintype "passive"))
      (node (ref "R9") (pin "2") (pinfunction "2_2") (pintype "passive"))
    )
    (net (code "36") (name "Net-(IC2D-OUT)") (class "Default")
      (node (ref "IC2") (pin "14") (pinfunction "OUT_14") (pintype "output"))
      (node (ref "R3") (pin "2") (pinfunction "2_2") (pintype "passive"))
      (node (ref "R7") (pin "1") (pinfunction "1_1") (pintype "passive"))
    )
    (net (code "37") (name "Net-(IC4A--IN)") (class "Default")
      (node (ref "IC4") (pin "1") (pinfunction "OUT_1") (pintype "output"))
      (node (ref "IC4") (pin "2") (pinfunction "-IN_2") (pintype "input"))
      (node (ref "OUTPUTLEVEL") (pin "P$3") (pinfunction "3_P$3") (pintype "passive"))
    )
    (net (code "38") (name "Net-(IC4B--IN)") (class "Default")
      (node (ref "IC4") (pin "6") (pinfunction "-IN_6") (pintype "input"))
      (node (ref "R5") (pin "2") (pinfunction "2_2") (pintype "passive"))
      (node (ref "R55") (pin "1") (pinfunction "1_1") (pintype "passive"))
      (node (ref "R56") (pin "1") (pinfunction "1_1") (pintype "passive"))
      (node (ref "R62") (pin "1") (pinfunction "1_1") (pintype "passive"))
    )
    (net (code "39") (name "Net-(IC4D--IN)") (class "Default")
      (node (ref "IC4") (pin "13") (pinfunction "-IN_13") (pintype "input"))
      (node (ref "IC4") (pin "14") (pinfunction "OUT_14") (pintype "output"))
      (node (ref "R79") (pin "2") (pinfunction "2_2") (pintype "passive"))
    )
    (net (code "40") (name "Net-(IC5A--IN)") (class "Default")
      (node (ref "IC5") (pin "2") (pinfunction "-IN_2") (pintype "input"))
      (node (ref "R6") (pin "1") (pinfunction "1_1") (pintype "passive"))
      (node (ref "R8") (pin "2") (pinfunction "2_2") (pintype "passive"))
    )
    (net (code "41") (name "Net-(IC5A-OUT)") (class "Default")
      (node (ref "IC5") (pin "1") (pinfunction "OUT_1") (pintype "output"))
      (node (ref "R6") (pin "2") (pinfunction "2_2") (pintype "passive"))
      (node (ref "R9") (pin "1") (pinfunction "1_1") (pintype "passive"))
    )
    (net (code "42") (name "Net-(IN1LEVEL-2)") (class "Default")
      (node (ref "IN1LEVEL") (pin "P$2") (pinfunction "2_P$2") (pintype "passive"))
      (node (ref "R55") (pin "2") (pinfunction "2_2") (pintype "passive"))
    )
    (net (code "43") (name "Net-(IN1LEVEL-3)") (class "Default")
      (node (ref "IN1") (pin "TIP") (pinfunction "TIP_TIP") (pintype "passive"))
      (node (ref "IN1LEVEL") (pin "P$3") (pinfunction "3_P$3") (pintype "passive"))
    )
    (net (code "44") (name "Net-(IN2LEVEL-2)") (class "Default")
      (node (ref "IN2LEVEL") (pin "P$2") (pinfunction "2_P$2") (pintype "passive"))
      (node (ref "R56") (pin "2") (pinfunction "2_2") (pintype "passive"))
    )
    (net (code "45") (name "Net-(IN2LEVEL-3)") (class "Default")
      (node (ref "IN2") (pin "TIP") (pinfunction "TIP_TIP") (pintype "passive"))
      (node (ref "IN2LEVEL") (pin "P$3") (pinfunction "3_P$3") (pintype "passive"))
    )
    (net (code "46") (name "Net-(IN3LEVEL-2)") (class "Default")
      (node (ref "IN3LEVEL") (pin "P$2") (pinfunction "2_P$2") (pintype "passive"))
      (node (ref "R62") (pin "2") (pinfunction "2_2") (pintype "passive"))
    )
    (net (code "47") (name "Net-(IN3LEVEL-3)") (class "Default")
      (node (ref "IN3") (pin "TIP") (pinfunction "TIP_TIP") (pintype "passive"))
      (node (ref "IN3LEVEL") (pin "P$3") (pinfunction "3_P$3") (pintype "passive"))
    )
    (net (code "48") (name "Net-(IN_GAIN-3)") (class "Default")
      (node (ref "IN_GAIN") (pin "P$3") (pinfunction "3_P$3") (pintype "passive"))
      (node (ref "R5") (pin "1") (pinfunction "1_1") (pintype "passive"))
    )
    (net (code "49") (name "Net-(IN_MIX-3)") (class "Default")
      (node (ref "IN_MIX") (pin "P3") (pinfunction "3_P3") (pintype "passive"))
      (node (ref "R79") (pin "1") (pinfunction "1_1") (pintype "passive"))
    )
    (net (code "50") (name "Net-(LED1A-A)") (class "Default")
      (node (ref "LED1") (pin "2") (pinfunction "A_2") (pintype "passive"))
      (node (ref "LED1") (pin "3") (pinfunction "C_3") (pintype "passive"))
      (node (ref "R1") (pin "1") (pinfunction "1_1") (pintype "passive"))
    )
    (net (code "51") (name "Net-(LED2A-A)") (class "Default")
      (node (ref "LED2") (pin "2") (pinfunction "A_2") (pintype "passive"))
      (node (ref "LED2") (pin "3") (pinfunction "C_3") (pintype "passive"))
      (node (ref "R4") (pin "1") (pinfunction "1_1") (pintype "passive"))
    )
    (net (code "52") (name "Net-(OUTPUT1-3)") (class "Default")
      (node (ref "OUTPUT1") (pin "P3") (pinfunction "3_P3") (pintype "passive"))
      (node (ref "R57") (pin "2") (pinfunction "2_2") (pintype "passive"))
    )
    (net (code "53") (name "Net-(OUTPUTLEVEL-2)") (class "Default")
      (node (ref "OUTPUTLEVEL") (pin "P$2") (pinfunction "2_P$2") (pintype "passive"))
      (node (ref "R57") (pin "1") (pinfunction "1_1") (pintype "passive"))
    )
    (net (code "54") (name "Net-(R60-E)") (class "Default")
      (node (ref "R3") (pin "1") (pinfunction "1_1") (pintype "passive"))
      (node (ref "R60") (pin "1") (pinfunction "E_1") (pintype "passive"))
      (node (ref "R60") (pin "2") (pinfunction "S_2") (pintype "passive"))
    )
    (net (code "55") (name "Net-(RES-2-2)") (class "Default")
      (node (ref "R71") (pin "1") (pinfunction "1_1") (pintype "passive"))
      (node (ref "RES-2") (pin "P2") (pinfunction "2_P2") (pintype "passive"))
    )
    (net (code "56") (name "Net-(RES-2-3)") (class "Default")
      (node (ref "D3") (pin "A") (pinfunction "A_A") (pintype "passive"))
      (node (ref "RES-2") (pin "P3") (pinfunction "3_P3") (pintype "passive"))
    )
    (net (code "57") (name "Net-(V-OCT1-3)") (class "Default")
      (node (ref "R59") (pin "1") (pinfunction "1_1") (pintype "passive"))
      (node (ref "V-OCT1") (pin "P3") (pinfunction "3_P3") (pintype "passive"))
    )
    (net (code "58") (name "RESONANCE_CTL2") (class "Default")
      (node (ref "R39") (pin "2") (pinfunction "2_2") (pintype "passive"))
      (node (ref "RESONANCE") (pin "P$2") (pinfunction "S_P$2") (pintype "passive"))
    )
    (net (code "59") (name "RESONANCE_IN2") (class "Default")
      (node (ref "IC4") (pin "8") (pinfunction "OUT_8") (pintype "output"))
      (node (ref "IC4") (pin "9") (pinfunction "-IN_9") (pintype "input"))
      (node (ref "RESONANCE") (pin "P$1") (pinfunction "E_P$1") (pintype "passive"))
    )
    (net (code "60") (name "unconnected-(IN1-SWITCH-PadNORM)") (class "Default")
      (node (ref "IN1") (pin "NORM") (pinfunction "SWITCH_NORM") (pintype "passive"))
    )
    (net (code "61") (name "unconnected-(IN2-SWITCH-PadNORM)") (class "Default")
      (node (ref "IN2") (pin "NORM") (pinfunction "SWITCH_NORM") (pintype "passive"))
    )
    (net (code "62") (name "unconnected-(IN3-SWITCH-PadNORM)") (class "Default")
      (node (ref "IN3") (pin "NORM") (pinfunction "SWITCH_NORM") (pintype "passive"))
    )
    (net (code "63") (name "unconnected-(IN_MIX-2-PadP2)") (class "Default")
      (node (ref "IN_MIX") (pin "P2") (pinfunction "2_P2") (pintype "passive"))
    )
    (net (code "64") (name "unconnected-(OUTPUT1-2-PadP2)") (class "Default")
      (node (ref "OUTPUT1") (pin "P2") (pinfunction "2_P2") (pintype "passive"))
    )
  )
)
